# display.net
KiCad netlist of a schematic drawn in Altium Designer
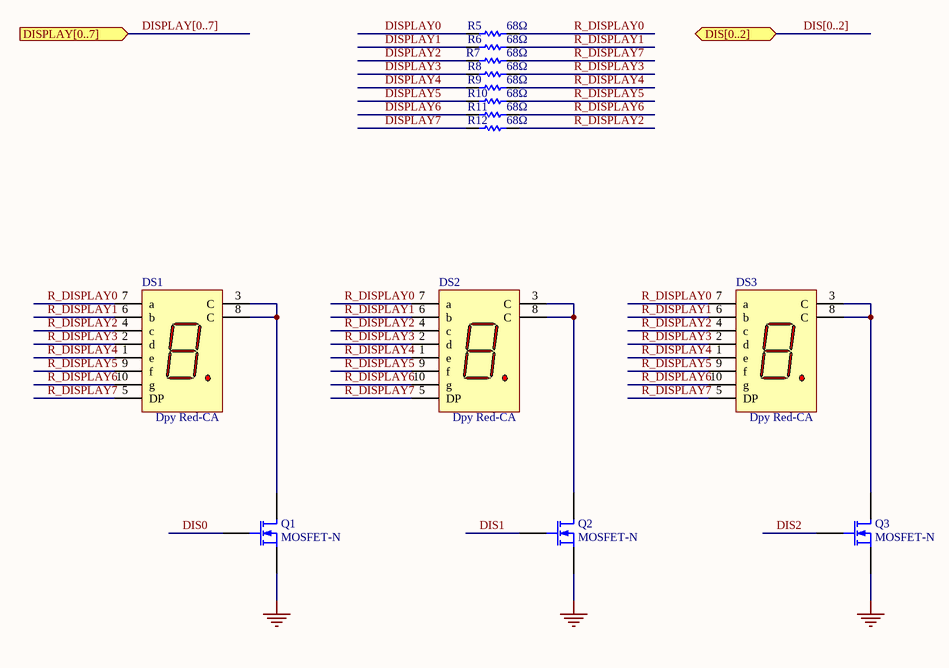
[diagram p0: display.SchDoc]

(export (version "E")
  (design (tool "Eeschema 10.0.6"))
  (components
    (comp (ref "DS1")
      (value "Dpy Red-CA")
      (footprint "DISPLAY")
      (description "Afficheur 7-Segment")
      (fields (field (name "PUBLISHER") "Altium Limited"))
      (libsource (lib "Miscellaneous Devices") (part "Dpy Red-CA"))
    )
    (comp (ref "DS2")
      (value "Dpy Red-CA")
      (footprint "DISPLAY")
      (description "Afficheur 7-Segment")
      (fields (field (name "PUBLISHER") "Altium Limited"))
      (libsource (lib "Miscellaneous Devices") (part "Dpy Red-CA"))
    )
    (comp (ref "DS3")
      (value "Dpy Red-CA")
      (footprint "DISPLAY")
      (description "Afficheur 7-Segment")
      (fields (field (name "PUBLISHER") "Altium Limited"))
      (libsource (lib "Miscellaneous Devices") (part "Dpy Red-CA"))
    )
    (comp (ref "Q1")
      (value "MOSFET-N")
      (footprint "MOSFET")
      (description "N-Channel MOSFET")
      (fields (field (name "PUBLISHER") "Altium Limited"))
      (libsource (lib "Miscellaneous Devices") (part "MOSFET-N"))
    )
    (comp (ref "Q2")
      (value "MOSFET-N")
      (footprint "MOSFET")
      (description "N-Channel MOSFET")
      (fields (field (name "PUBLISHER") "Altium Limited"))
      (libsource (lib "Miscellaneous Devices") (part "MOSFET-N"))
    )
    (comp (ref "Q3")
      (value "MOSFET-N")
      (footprint "MOSFET")
      (description "N-Channel MOSFET")
      (fields (field (name "PUBLISHER") "Altium Limited"))
      (libsource (lib "Miscellaneous Devices") (part "MOSFET-N"))
    )
    (comp (ref "R5")
      (value "68Ω")
      (footprint "RESISTANCE")
      (description "Resistor")
      (fields (field (name "Comment") "Res1") (field (name "PUBLISHER") "Altium Limited"))
      (libsource (lib "PCB_DEPP") (part "Res1"))
    )
    (comp (ref "R6")
      (value "68Ω")
      (footprint "RESISTANCE")
      (description "Resistor")
      (fields (field (name "Comment") "Res1") (field (name "PUBLISHER") "Altium Limited"))
      (libsource (lib "PCB_DEPP") (part "Res1"))
    )
    (comp (ref "R7")
      (value "68Ω")
      (footprint "RESISTANCE")
      (description "Resistor")
      (fields (field (name "Comment") "Res1") (field (name "PUBLISHER") "Altium Limited"))
      (libsource (lib "PCB_DEPP") (part "Res1"))
    )
    (comp (ref "R8")
      (value "68Ω")
      (footprint "RESISTANCE")
      (description "Resistor")
      (fields (field (name "Comment") "Res1") (field (name "PUBLISHER") "Altium Limited"))
      (libsource (lib "PCB_DEPP") (part "Res1"))
    )
    (comp (ref "R9")
      (value "68Ω")
      (footprint "RESISTANCE")
      (description "Resistor")
      (fields (field (name "Comment") "Res1") (field (name "PUBLISHER") "Altium Limited"))
      (libsource (lib "PCB_DEPP") (part "Res1"))
    )
    (comp (ref "R10")
      (value "68Ω")
      (footprint "RESISTANCE")
      (description "Resistor")
      (fields (field (name "Comment") "Res1") (field (name "PUBLISHER") "Altium Limited"))
      (libsource (lib "PCB_DEPP") (part "Res1"))
    )
    (comp (ref "R11")
      (value "68Ω")
      (footprint "RESISTANCE")
      (description "Resistor")
      (fields (field (name "Comment") "Res1") (field (name "PUBLISHER") "Altium Limited"))
      (libsource (lib "PCB_DEPP") (part "Res1"))
    )
    (comp (ref "R12")
      (value "68Ω")
      (footprint "RESISTANCE")
      (description "Resistor")
      (fields (field (name "Comment") "Res1") (field (name "PUBLISHER") "Altium Limited"))
      (libsource (lib "PCB_DEPP") (part "Res1"))
    )
  )
  (nets
    (net (code "1") (name "/DIS0") (class "Default")
      (node (ref "Q1") (pin "2") (pinfunction "G_2") (pintype "passive"))
    )
    (net (code "2") (name "/DIS1") (class "Default")
      (node (ref "Q2") (pin "2") (pinfunction "G_2") (pintype "passive"))
    )
    (net (code "3") (name "/DIS2") (class "Default")
      (node (ref "Q3") (pin "2") (pinfunction "G_2") (pintype "passive"))
    )
    (net (code "4") (name "/DISPLAY0") (class "Default")
      (node (ref "R5") (pin "1") (pinfunction "1_1") (pintype "passive"))
    )
    (net (code "5") (name "/DISPLAY1") (class "Default")
      (node (ref "R6") (pin "1") (pinfunction "1_1") (pintype "passive"))
    )
    (net (code "6") (name "/DISPLAY2") (class "Default")
      (node (ref "R7") (pin "1") (pinfunction "1_1") (pintype "passive"))
    )
    (net (code "7") (name "/DISPLAY3") (class "Default")
      (node (ref "R8") (pin "1") (pinfunction "1_1") (pintype "passive"))
    )
    (net (code "8") (name "/DISPLAY4") (class "Default")
      (node (ref "R9") (pin "1") (pinfunction "1_1") (pintype "passive"))
    )
    (net (code "9") (name "/DISPLAY5") (class "Default")
      (node (ref "R10") (pin "1") (pinfunction "1_1") (pintype "passive"))
    )
    (net (code "10") (name "/DISPLAY6") (class "Default")
      (node (ref "R11") (pin "1") (pinfunction "1_1") (pintype "passive"))
    )
    (net (code "11") (name "/DISPLAY7") (class "Default")
      (node (ref "R12") (pin "1") (pinfunction "1_1") (pintype "passive"))
    )
    (net (code "14") (name "/R_DISPLAY0") (class "Default")
      (node (ref "DS1") (pin "7") (pinfunction "a_7") (pintype "passive"))
      (node (ref "DS2") (pin "7") (pinfunction "a_7") (pintype "passive"))
      (node (ref "DS3") (pin "7") (pinfunction "a_7") (pintype "passive"))
      (node (ref "R5") (pin "2") (pinfunction "2_2") (pintype "passive"))
    )
    (net (code "15") (name "/R_DISPLAY1") (class "Default")
      (node (ref "DS1") (pin "6") (pinfunction "b_6") (pintype "passive"))
      (node (ref "DS2") (pin "6") (pinfunction "b_6") (pintype "passive"))
      (node (ref "DS3") (pin "6") (pinfunction "b_6") (pintype "passive"))
      (node (ref "R6") (pin "2") (pinfunction "2_2") (pintype "passive"))
    )
    (net (code "16") (name "/R_DISPLAY2") (class "Default")
      (node (ref "DS1") (pin "4") (pinfunction "c_4") (pintype "passive"))
      (node (ref "DS2") (pin "4") (pinfunction "c_4") (pintype "passive"))
      (node (ref "DS3") (pin "4") (pinfunction "c_4") (pintype "passive"))
      (node (ref "R12") (pin "2") (pinfunction "2_2") (pintype "passive"))
    )
    (net (code "17") (name "/R_DISPLAY3") (class "Default")
      (node (ref "DS1") (pin "2") (pinfunction "d_2") (pintype "passive"))
      (node (ref "DS2") (pin "2") (pinfunction "d_2") (pintype "passive"))
      (node (ref "DS3") (pin "2") (pinfunction "d_2") (pintype "passive"))
      (node (ref "R8") (pin "2") (pinfunction "2_2") (pintype "passive"))
    )
    (net (code "18") (name "/R_DISPLAY4") (class "Default")
      (node (ref "DS1") (pin "1") (pinfunction "e_1") (pintype "passive"))
      (node (ref "DS2") (pin "1") (pinfunction "e_1") (pintype "passive"))
      (node (ref "DS3") (pin "1") (pinfunction "e_1") (pintype "passive"))
      (node (ref "R9") (pin "2") (pinfunction "2_2") (pintype "passive"))
    )
    (net (code "19") (name "/R_DISPLAY5") (class "Default")
      (node (ref "DS1") (pin "9") (pinfunction "f_9") (pintype "passive"))
      (node (ref "DS2") (pin "9") (pinfunction "f_9") (pintype "passive"))
      (node (ref "DS3") (pin "9") (pinfunction "f_9") (pintype "passive"))
      (node (ref "R10") (pin "2") (pinfunction "2_2") (pintype "passive"))
    )
    (net (code "20") (name "/R_DISPLAY6") (class "Default")
      (node (ref "DS1") (pin "10") (pinfunction "g_10") (pintype "passive"))
      (node (ref "DS2") (pin "10") (pinfunction "g_10") (pintype "passive"))
      (node (ref "DS3") (pin "10") (pinfunction "g_10") (pintype "passive"))
      (node (ref "R11") (pin "2") (pinfunction "2_2") (pintype "passive"))
    )
    (net (code "21") (name "/R_DISPLAY7") (class "Default")
      (node (ref "DS1") (pin "5") (pinfunction "DP_5") (pintype "passive"))
      (node (ref "DS2") (pin "5") (pinfunction "DP_5") (pintype "passive"))
      (node (ref "DS3") (pin "5") (pinfunction "DP_5") (pintype "passive"))
      (node (ref "R7") (pin "2") (pinfunction "2_2") (pintype "passive"))
    )
    (net (code "22") (name "GND") (class "Default")
      (node (ref "Q1") (pin "3") (pinfunction "S_3") (pintype "passive"))
      (node (ref "Q2") (pin "3") (pinfunction "S_3") (pintype "passive"))
      (node (ref "Q3") (pin "3") (pinfunction "S_3") (pintype "passive"))
    )
    (net (code "23") (name "Net-(Q1-D)") (class "Default")
      (node (ref "DS1") (pin "3") (pinfunction "C_3") (pintype "passive"))
      (node (ref "DS1") (pin "8") (pinfunction "C_8") (pintype "passive"))
      (node (ref "Q1") (pin "1") (pinfunction "D_1") (pintype "passive"))
    )
    (net (code "24") (name "Net-(Q2-D)") (class "Default")
      (node (ref "DS2") (pin "3") (pinfunction "C_3") (pintype "passive"))
      (node (ref "DS2") (pin "8") (pinfunction "C_8") (pintype "passive"))
      (node (ref "Q2") (pin "1") (pinfunction "D_1") (pintype "passive"))
    )
    (net (code "25") (name "Net-(Q3-D)") (class "Default")
      (node (ref "DS3") (pin "3") (pinfunction "C_3") (pintype "passive"))
      (node (ref "DS3") (pin "8") (pinfunction "C_8") (pintype "passive"))
      (node (ref "Q3") (pin "1") (pinfunction "D_1") (pintype "passive"))
    )
  )
)
